# module_adapters.net
KiCad netlist of a schematic drawn in Altium Designer
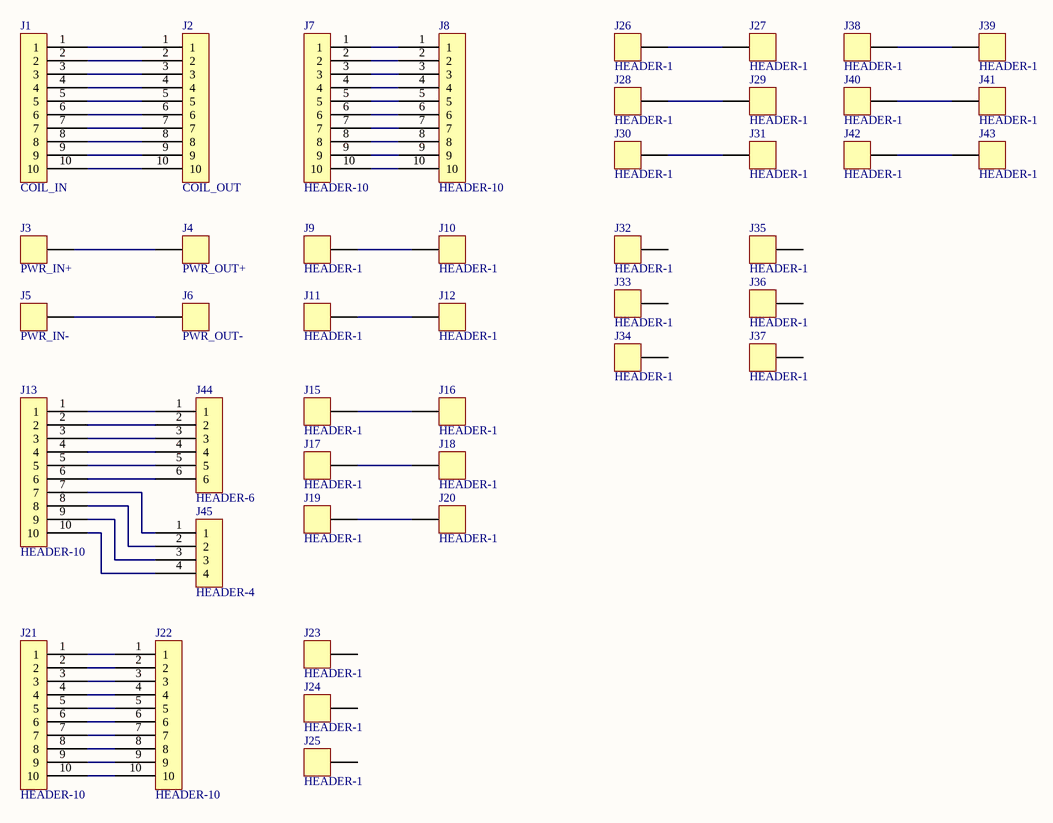
[diagram p0: module_adapters.SchDoc]

(export (version "E")
  (design (tool "Eeschema 10.0.6"))
  (components
    (comp (ref "J1") (value "COIL_IN") (footprint "MICRO-MATCH-10") (libsource (lib "") (part "HEADER-10_1")))
    (comp (ref "J2")
      (value "COIL_OUT")
      (footprint "MICRO-MATCH-MOB-10")
      (libsource (lib "connectors") (part "HEADER-10"))
    )
    (comp (ref "J3")
      (value "PWR_IN+")
      (footprint "HIGH-POWER-VIA")
      (libsource (lib "connectors") (part "HEADER-1"))
    )
    (comp (ref "J4") (value "PWR_OUT+") (footprint "2MM-BANANA-VIA") (libsource (lib "") (part "HEADER-1_1")))
    (comp (ref "J5")
      (value "PWR_IN-")
      (footprint "HIGH-POWER-VIA")
      (libsource (lib "connectors") (part "HEADER-1"))
    )
    (comp (ref "J6") (value "PWR_OUT-") (footprint "2MM-BANANA-VIA") (libsource (lib "") (part "HEADER-1_1")))
    (comp (ref "J7")
      (value "HEADER-10")
      (footprint "MICRO-MATCH-10")
      (libsource (lib "") (part "HEADER-10_1"))
    )
    (comp (ref "J8")
      (value "HEADER-10")
      (footprint "MICRO-MATCH-10")
      (libsource (lib "connectors") (part "HEADER-10"))
    )
    (comp (ref "J9")
      (value "HEADER-1")
      (footprint "2MM-BULLET-PLUG-VIA")
      (libsource (lib "connectors") (part "HEADER-1"))
    )
    (comp (ref "J10")
      (value "HEADER-1")
      (footprint "HIGH-POWER-VIA")
      (libsource (lib "") (part "HEADER-1_1"))
    )
    (comp (ref "J11")
      (value "HEADER-1")
      (footprint "2MM-BULLET-PLUG-VIA")
      (libsource (lib "connectors") (part "HEADER-1"))
    )
    (comp (ref "J12")
      (value "HEADER-1")
      (footprint "HIGH-POWER-VIA")
      (libsource (lib "") (part "HEADER-1_1"))
    )
    (comp (ref "J13")
      (value "HEADER-10")
      (footprint "MICRO-MATCH-10")
      (libsource (lib "") (part "HEADER-10_1"))
    )
    (comp (ref "J15")
      (value "HEADER-1")
      (footprint "2MM-BULLET-PLUG-VIA")
      (libsource (lib "connectors") (part "HEADER-1"))
    )
    (comp (ref "J16")
      (value "HEADER-1")
      (footprint "2MM-BANANA-VIA")
      (libsource (lib "") (part "HEADER-1_1"))
    )
    (comp (ref "J17")
      (value "HEADER-1")
      (footprint "2MM-BULLET-PLUG-VIA")
      (libsource (lib "connectors") (part "HEADER-1"))
    )
    (comp (ref "J18")
      (value "HEADER-1")
      (footprint "2MM-BANANA-VIA")
      (libsource (lib "") (part "HEADER-1_1"))
    )
    (comp (ref "J19")
      (value "HEADER-1")
      (footprint "2MM-BULLET-PLUG-VIA")
      (libsource (lib "connectors") (part "HEADER-1"))
    )
    (comp (ref "J20")
      (value "HEADER-1")
      (footprint "2MM-BANANA-VIA")
      (libsource (lib "") (part "HEADER-1_1"))
    )
    (comp (ref "J21")
      (value "HEADER-10")
      (footprint "MICRO-MATCH-10")
      (libsource (lib "") (part "HEADER-10_1"))
    )
    (comp (ref "J22")
      (value "HEADER-10")
      (footprint "MICRO-MATCH-MOB-10")
      (libsource (lib "connectors") (part "HEADER-10"))
    )
    (comp (ref "J23")
      (value "HEADER-1")
      (footprint "2MM-BANANA-VIA")
      (libsource (lib "connectors") (part "HEADER-1"))
    )
    (comp (ref "J24")
      (value "HEADER-1")
      (footprint "2MM-BANANA-VIA")
      (libsource (lib "connectors") (part "HEADER-1"))
    )
    (comp (ref "J25")
      (value "HEADER-1")
      (footprint "2MM-BANANA-VIA")
      (libsource (lib "connectors") (part "HEADER-1"))
    )
    (comp (ref "J26")
      (value "HEADER-1")
      (footprint "2MM-BULLET-PLUG-VIA")
      (libsource (lib "connectors") (part "HEADER-1"))
    )
    (comp (ref "J27")
      (value "HEADER-1")
      (footprint "HIGH-POWER-VIA")
      (libsource (lib "") (part "HEADER-1_1"))
    )
    (comp (ref "J28")
      (value "HEADER-1")
      (footprint "2MM-BULLET-PLUG-VIA")
      (libsource (lib "connectors") (part "HEADER-1"))
    )
    (comp (ref "J29")
      (value "HEADER-1")
      (footprint "HIGH-POWER-VIA")
      (libsource (lib "") (part "HEADER-1_1"))
    )
    (comp (ref "J30")
      (value "HEADER-1")
      (footprint "2MM-BULLET-PLUG-VIA")
      (libsource (lib "connectors") (part "HEADER-1"))
    )
    (comp (ref "J31")
      (value "HEADER-1")
      (footprint "HIGH-POWER-VIA")
      (libsource (lib "") (part "HEADER-1_1"))
    )
    (comp (ref "J32")
      (value "HEADER-1")
      (footprint "2MM-BANANA-VIA")
      (libsource (lib "connectors") (part "HEADER-1"))
    )
    (comp (ref "J33")
      (value "HEADER-1")
      (footprint "2MM-BANANA-VIA")
      (libsource (lib "connectors") (part "HEADER-1"))
    )
    (comp (ref "J34")
      (value "HEADER-1")
      (footprint "2MM-BANANA-VIA")
      (libsource (lib "connectors") (part "HEADER-1"))
    )
    (comp (ref "J35")
      (value "HEADER-1")
      (footprint "2MM-BANANA-VIA")
      (libsource (lib "connectors") (part "HEADER-1"))
    )
    (comp (ref "J36")
      (value "HEADER-1")
      (footprint "2MM-BANANA-VIA")
      (libsource (lib "connectors") (part "HEADER-1"))
    )
    (comp (ref "J37")
      (value "HEADER-1")
      (footprint "2MM-BANANA-VIA")
      (libsource (lib "connectors") (part "HEADER-1"))
    )
    (comp (ref "J38")
      (value "HEADER-1")
      (footprint "2MM-BULLET-PLUG-VIA")
      (libsource (lib "connectors") (part "HEADER-1"))
    )
    (comp (ref "J39")
      (value "HEADER-1")
      (footprint "HIGH-POWER-VIA")
      (libsource (lib "") (part "HEADER-1_1"))
    )
    (comp (ref "J40")
      (value "HEADER-1")
      (footprint "2MM-BULLET-PLUG-VIA")
      (libsource (lib "connectors") (part "HEADER-1"))
    )
    (comp (ref "J41")
      (value "HEADER-1")
      (footprint "HIGH-POWER-VIA")
      (libsource (lib "") (part "HEADER-1_1"))
    )
    (comp (ref "J42")
      (value "HEADER-1")
      (footprint "2MM-BULLET-PLUG-VIA")
      (libsource (lib "connectors") (part "HEADER-1"))
    )
    (comp (ref "J43")
      (value "HEADER-1")
      (footprint "HIGH-POWER-VIA")
      (libsource (lib "") (part "HEADER-1_1"))
    )
    (comp (ref "J44")
      (value "HEADER-6")
      (footprint "MICRO-MATCH-6")
      (libsource (lib "connectors") (part "HEADER-6"))
    )
    (comp (ref "J45")
      (value "HEADER-4")
      (footprint "MICRO-MATCH-4")
      (libsource (lib "connectors") (part "HEADER-4"))
    )
  )
  (nets
    (net (code "1") (name "Net-(J1-Pad1)") (class "Default")
      (node (ref "J1") (pin "1") (pinfunction "1_1") (pintype "passive"))
      (node (ref "J2") (pin "1") (pinfunction "1_1") (pintype "passive"))
    )
    (net (code "2") (name "Net-(J1-Pad2)") (class "Default")
      (node (ref "J1") (pin "2") (pinfunction "2_2") (pintype "passive"))
      (node (ref "J2") (pin "2") (pinfunction "2_2") (pintype "passive"))
    )
    (net (code "3") (name "Net-(J1-Pad3)") (class "Default")
      (node (ref "J1") (pin "3") (pinfunction "3_3") (pintype "passive"))
      (node (ref "J2") (pin "3") (pinfunction "3_3") (pintype "passive"))
    )
    (net (code "4") (name "Net-(J1-Pad4)") (class "Default")
      (node (ref "J1") (pin "4") (pinfunction "4_4") (pintype "passive"))
      (node (ref "J2") (pin "4") (pinfunction "4_4") (pintype "passive"))
    )
    (net (code "5") (name "Net-(J1-Pad5)") (class "Default")
      (node (ref "J1") (pin "5") (pinfunction "5_5") (pintype "passive"))
      (node (ref "J2") (pin "5") (pinfunction "5_5") (pintype "passive"))
    )
    (net (code "6") (name "Net-(J1-Pad6)") (class "Default")
      (node (ref "J1") (pin "6") (pinfunction "6_6") (pintype "passive"))
      (node (ref "J2") (pin "6") (pinfunction "6_6") (pintype "passive"))
    )
    (net (code "7") (name "Net-(J1-Pad7)") (class "Default")
      (node (ref "J1") (pin "7") (pinfunction "7_7") (pintype "passive"))
      (node (ref "J2") (pin "7") (pinfunction "7_7") (pintype "passive"))
    )
    (net (code "8") (name "Net-(J1-Pad8)") (class "Default")
      (node (ref "J1") (pin "8") (pinfunction "8_8") (pintype "passive"))
      (node (ref "J2") (pin "8") (pinfunction "8_8") (pintype "passive"))
    )
    (net (code "9") (name "Net-(J1-Pad9)") (class "Default")
      (node (ref "J1") (pin "9") (pinfunction "9_9") (pintype "passive"))
      (node (ref "J2") (pin "9") (pinfunction "9_9") (pintype "passive"))
    )
    (net (code "10") (name "Net-(J1-Pad10)") (class "Default")
      (node (ref "J1") (pin "10") (pinfunction "10_10") (pintype "passive"))
      (node (ref "J2") (pin "10") (pinfunction "10_10") (pintype "passive"))
    )
    (net (code "11") (name "Net-(J3-Pad1)") (class "Default")
      (node (ref "J3") (pin "1") (pinfunction "1_1") (pintype "passive"))
      (node (ref "J4") (pin "1") (pinfunction "1_1") (pintype "passive"))
    )
    (net (code "12") (name "Net-(J5-Pad1)") (class "Default")
      (node (ref "J5") (pin "1") (pinfunction "1_1") (pintype "passive"))
      (node (ref "J6") (pin "1") (pinfunction "1_1") (pintype "passive"))
    )
    (net (code "13") (name "Net-(J7-Pad1)") (class "Default")
      (node (ref "J7") (pin "1") (pinfunction "1_1") (pintype "passive"))
      (node (ref "J8") (pin "1") (pinfunction "1_1") (pintype "passive"))
    )
    (net (code "14") (name "Net-(J7-Pad2)") (class "Default")
      (node (ref "J7") (pin "2") (pinfunction "2_2") (pintype "passive"))
      (node (ref "J8") (pin "2") (pinfunction "2_2") (pintype "passive"))
    )
    (net (code "15") (name "Net-(J7-Pad3)") (class "Default")
      (node (ref "J7") (pin "3") (pinfunction "3_3") (pintype "passive"))
      (node (ref "J8") (pin "3") (pinfunction "3_3") (pintype "passive"))
    )
    (net (code "16") (name "Net-(J7-Pad4)") (class "Default")
      (node (ref "J7") (pin "4") (pinfunction "4_4") (pintype "passive"))
      (node (ref "J8") (pin "4") (pinfunction "4_4") (pintype "passive"))
    )
    (net (code "17") (name "Net-(J7-Pad5)") (class "Default")
      (node (ref "J7") (pin "5") (pinfunction "5_5") (pintype "passive"))
      (node (ref "J8") (pin "5") (pinfunction "5_5") (pintype "passive"))
    )
    (net (code "18") (name "Net-(J7-Pad6)") (class "Default")
      (node (ref "J7") (pin "6") (pinfunction "6_6") (pintype "passive"))
      (node (ref "J8") (pin "6") (pinfunction "6_6") (pintype "passive"))
    )
    (net (code "19") (name "Net-(J7-Pad7)") (class "Default")
      (node (ref "J7") (pin "7") (pinfunction "7_7") (pintype "passive"))
      (node (ref "J8") (pin "7") (pinfunction "7_7") (pintype "passive"))
    )
    (net (code "20") (name "Net-(J7-Pad8)") (class "Default")
      (node (ref "J7") (pin "8") (pinfunction "8_8") (pintype "passive"))
      (node (ref "J8") (pin "8") (pinfunction "8_8") (pintype "passive"))
    )
    (net (code "21") (name "Net-(J7-Pad9)") (class "Default")
      (node (ref "J7") (pin "9") (pinfunction "9_9") (pintype "passive"))
      (node (ref "J8") (pin "9") (pinfunction "9_9") (pintype "passive"))
    )
    (net (code "22") (name "Net-(J7-Pad10)") (class "Default")
      (node (ref "J7") (pin "10") (pinfunction "10_10") (pintype "passive"))
      (node (ref "J8") (pin "10") (pinfunction "10_10") (pintype "passive"))
    )
    (net (code "23") (name "Net-(J10-Pad1)") (class "Default")
      (node (ref "J10") (pin "1") (pinfunction "1_1") (pintype "passive"))
      (node (ref "J9") (pin "1") (pinfunction "1_1") (pintype "passive"))
    )
    (net (code "24") (name "Net-(J11-Pad1)") (class "Default")
      (node (ref "J11") (pin "1") (pinfunction "1_1") (pintype "passive"))
      (node (ref "J12") (pin "1") (pinfunction "1_1") (pintype "passive"))
    )
    (net (code "25") (name "Net-(J13-Pad1)") (class "Default")
      (node (ref "J13") (pin "1") (pinfunction "1_1") (pintype "passive"))
      (node (ref "J44") (pin "1") (pinfunction "1_1") (pintype "passive"))
    )
    (net (code "26") (name "Net-(J13-Pad2)") (class "Default")
      (node (ref "J13") (pin "2") (pinfunction "2_2") (pintype "passive"))
      (node (ref "J44") (pin "2") (pinfunction "2_2") (pintype "passive"))
    )
    (net (code "27") (name "Net-(J13-Pad3)") (class "Default")
      (node (ref "J13") (pin "3") (pinfunction "3_3") (pintype "passive"))
      (node (ref "J44") (pin "3") (pinfunction "3_3") (pintype "passive"))
    )
    (net (code "28") (name "Net-(J13-Pad4)") (class "Default")
      (node (ref "J13") (pin "4") (pinfunction "4_4") (pintype "passive"))
      (node (ref "J44") (pin "4") (pinfunction "4_4") (pintype "passive"))
    )
    (net (code "29") (name "Net-(J13-Pad5)") (class "Default")
      (node (ref "J13") (pin "5") (pinfunction "5_5") (pintype "passive"))
      (node (ref "J44") (pin "5") (pinfunction "5_5") (pintype "passive"))
    )
    (net (code "30") (name "Net-(J13-Pad6)") (class "Default")
      (node (ref "J13") (pin "6") (pinfunction "6_6") (pintype "passive"))
      (node (ref "J44") (pin "6") (pinfunction "6_6") (pintype "passive"))
    )
    (net (code "31") (name "Net-(J13-Pad7)") (class "Default")
      (node (ref "J13") (pin "7") (pinfunction "7_7") (pintype "passive"))
      (node (ref "J45") (pin "1") (pinfunction "1_1") (pintype "passive"))
    )
    (net (code "32") (name "Net-(J13-Pad8)") (class "Default")
      (node (ref "J13") (pin "8") (pinfunction "8_8") (pintype "passive"))
      (node (ref "J45") (pin "2") (pinfunction "2_2") (pintype "passive"))
    )
    (net (code "33") (name "Net-(J13-Pad9)") (class "Default")
      (node (ref "J13") (pin "9") (pinfunction "9_9") (pintype "passive"))
      (node (ref "J45") (pin "3") (pinfunction "3_3") (pintype "passive"))
    )
    (net (code "34") (name "Net-(J13-Pad10)") (class "Default")
      (node (ref "J13") (pin "10") (pinfunction "10_10") (pintype "passive"))
      (node (ref "J45") (pin "4") (pinfunction "4_4") (pintype "passive"))
    )
    (net (code "35") (name "Net-(J15-Pad1)") (class "Default")
      (node (ref "J15") (pin "1") (pinfunction "1_1") (pintype "passive"))
      (node (ref "J16") (pin "1") (pinfunction "1_1") (pintype "passive"))
    )
    (net (code "36") (name "Net-(J17-Pad1)") (class "Default")
      (node (ref "J17") (pin "1") (pinfunction "1_1") (pintype "passive"))
      (node (ref "J18") (pin "1") (pinfunction "1_1") (pintype "passive"))
    )
    (net (code "37") (name "Net-(J19-Pad1)") (class "Default")
      (node (ref "J19") (pin "1") (pinfunction "1_1") (pintype "passive"))
      (node (ref "J20") (pin "1") (pinfunction "1_1") (pintype "passive"))
    )
    (net (code "38") (name "Net-(J21-Pad1)") (class "Default")
      (node (ref "J21") (pin "1") (pinfunction "1_1") (pintype "passive"))
      (node (ref "J22") (pin "1") (pinfunction "1_1") (pintype "passive"))
    )
    (net (code "39") (name "Net-(J21-Pad2)") (class "Default")
      (node (ref "J21") (pin "2") (pinfunction "2_2") (pintype "passive"))
      (node (ref "J22") (pin "2") (pinfunction "2_2") (pintype "passive"))
    )
    (net (code "40") (name "Net-(J21-Pad3)") (class "Default")
      (node (ref "J21") (pin "3") (pinfunction "3_3") (pintype "passive"))
      (node (ref "J22") (pin "3") (pinfunction "3_3") (pintype "passive"))
    )
    (net (code "41") (name "Net-(J21-Pad4)") (class "Default")
      (node (ref "J21") (pin "4") (pinfunction "4_4") (pintype "passive"))
      (node (ref "J22") (pin "4") (pinfunction "4_4") (pintype "passive"))
    )
    (net (code "42") (name "Net-(J21-Pad5)") (class "Default")
      (node (ref "J21") (pin "5") (pinfunction "5_5") (pintype "passive"))
      (node (ref "J22") (pin "5") (pinfunction "5_5") (pintype "passive"))
    )
    (net (code "43") (name "Net-(J21-Pad6)") (class "Default")
      (node (ref "J21") (pin "6") (pinfunction "6_6") (pintype "passive"))
      (node (ref "J22") (pin "6") (pinfunction "6_6") (pintype "passive"))
    )
    (net (code "44") (name "Net-(J21-Pad7)") (class "Default")
      (node (ref "J21") (pin "7") (pinfunction "7_7") (pintype "passive"))
      (node (ref "J22") (pin "7") (pinfunction "7_7") (pintype "passive"))
    )
    (net (code "45") (name "Net-(J21-Pad8)") (class "Default")
      (node (ref "J21") (pin "8") (pinfunction "8_8") (pintype "passive"))
      (node (ref "J22") (pin "8") (pinfunction "8_8") (pintype "passive"))
    )
    (net (code "46") (name "Net-(J21-Pad9)") (class "Default")
      (node (ref "J21") (pin "9") (pinfunction "9_9") (pintype "passive"))
      (node (ref "J22") (pin "9") (pinfunction "9_9") (pintype "passive"))
    )
    (net (code "47") (name "Net-(J21-Pad10)") (class "Default")
      (node (ref "J21") (pin "10") (pinfunction "10_10") (pintype "passive"))
      (node (ref "J22") (pin "10") (pinfunction "10_10") (pintype "passive"))
    )
    (net (code "48") (name "Net-(J26-Pad1)") (class "Default")
      (node (ref "J26") (pin "1") (pinfunction "1_1") (pintype "passive"))
      (node (ref "J27") (pin "1") (pinfunction "1_1") (pintype "passive"))
    )
    (net (code "49") (name "Net-(J28-Pad1)") (class "Default")
      (node (ref "J28") (pin "1") (pinfunction "1_1") (pintype "passive"))
      (node (ref "J29") (pin "1") (pinfunction "1_1") (pintype "passive"))
    )
    (net (code "50") (name "Net-(J30-Pad1)") (class "Default")
      (node (ref "J30") (pin "1") (pinfunction "1_1") (pintype "passive"))
      (node (ref "J31") (pin "1") (pinfunction "1_1") (pintype "passive"))
    )
    (net (code "51") (name "Net-(J38-Pad1)") (class "Default")
      (node (ref "J38") (pin "1") (pinfunction "1_1") (pintype "passive"))
      (node (ref "J39") (pin "1") (pinfunction "1_1") (pintype "passive"))
    )
    (net (code "52") (name "Net-(J40-Pad1)") (class "Default")
      (node (ref "J40") (pin "1") (pinfunction "1_1") (pintype "passive"))
      (node (ref "J41") (pin "1") (pinfunction "1_1") (pintype "passive"))
    )
    (net (code "53") (name "Net-(J42-Pad1)") (class "Default")
      (node (ref "J42") (pin "1") (pinfunction "1_1") (pintype "passive"))
      (node (ref "J43") (pin "1") (pinfunction "1_1") (pintype "passive"))
    )
    (net (code "54") (name "unconnected-(J23-Pad1)") (class "Default")
      (node (ref "J23") (pin "1") (pinfunction "1_1") (pintype "passive"))
    )
    (net (code "55") (name "unconnected-(J24-Pad1)") (class "Default")
      (node (ref "J24") (pin "1") (pinfunction "1_1") (pintype "passive"))
    )
    (net (code "56") (name "unconnected-(J25-Pad1)") (class "Default")
      (node (ref "J25") (pin "1") (pinfunction "1_1") (pintype "passive"))
    )
    (net (code "57") (name "unconnected-(J32-Pad1)") (class "Default")
      (node (ref "J32") (pin "1") (pinfunction "1_1") (pintype "passive"))
    )
    (net (code "58") (name "unconnected-(J33-Pad1)") (class "Default")
      (node (ref "J33") (pin "1") (pinfunction "1_1") (pintype "passive"))
    )
    (net (code "59") (name "unconnected-(J34-Pad1)") (class "Default")
      (node (ref "J34") (pin "1") (pinfunction "1_1") (pintype "passive"))
    )
    (net (code "60") (name "unconnected-(J35-Pad1)") (class "Default")
      (node (ref "J35") (pin "1") (pinfunction "1_1") (pintype "passive"))
    )
    (net (code "61") (name "unconnected-(J36-Pad1)") (class "Default")
      (node (ref "J36") (pin "1") (pinfunction "1_1") (pintype "passive"))
    )
    (net (code "62") (name "unconnected-(J37-Pad1)") (class "Default")
      (node (ref "J37") (pin "1") (pinfunction "1_1") (pintype "passive"))
    )
  )
)
